# controller-adapter.net
KiCad netlist of a schematic drawn in EAGLE
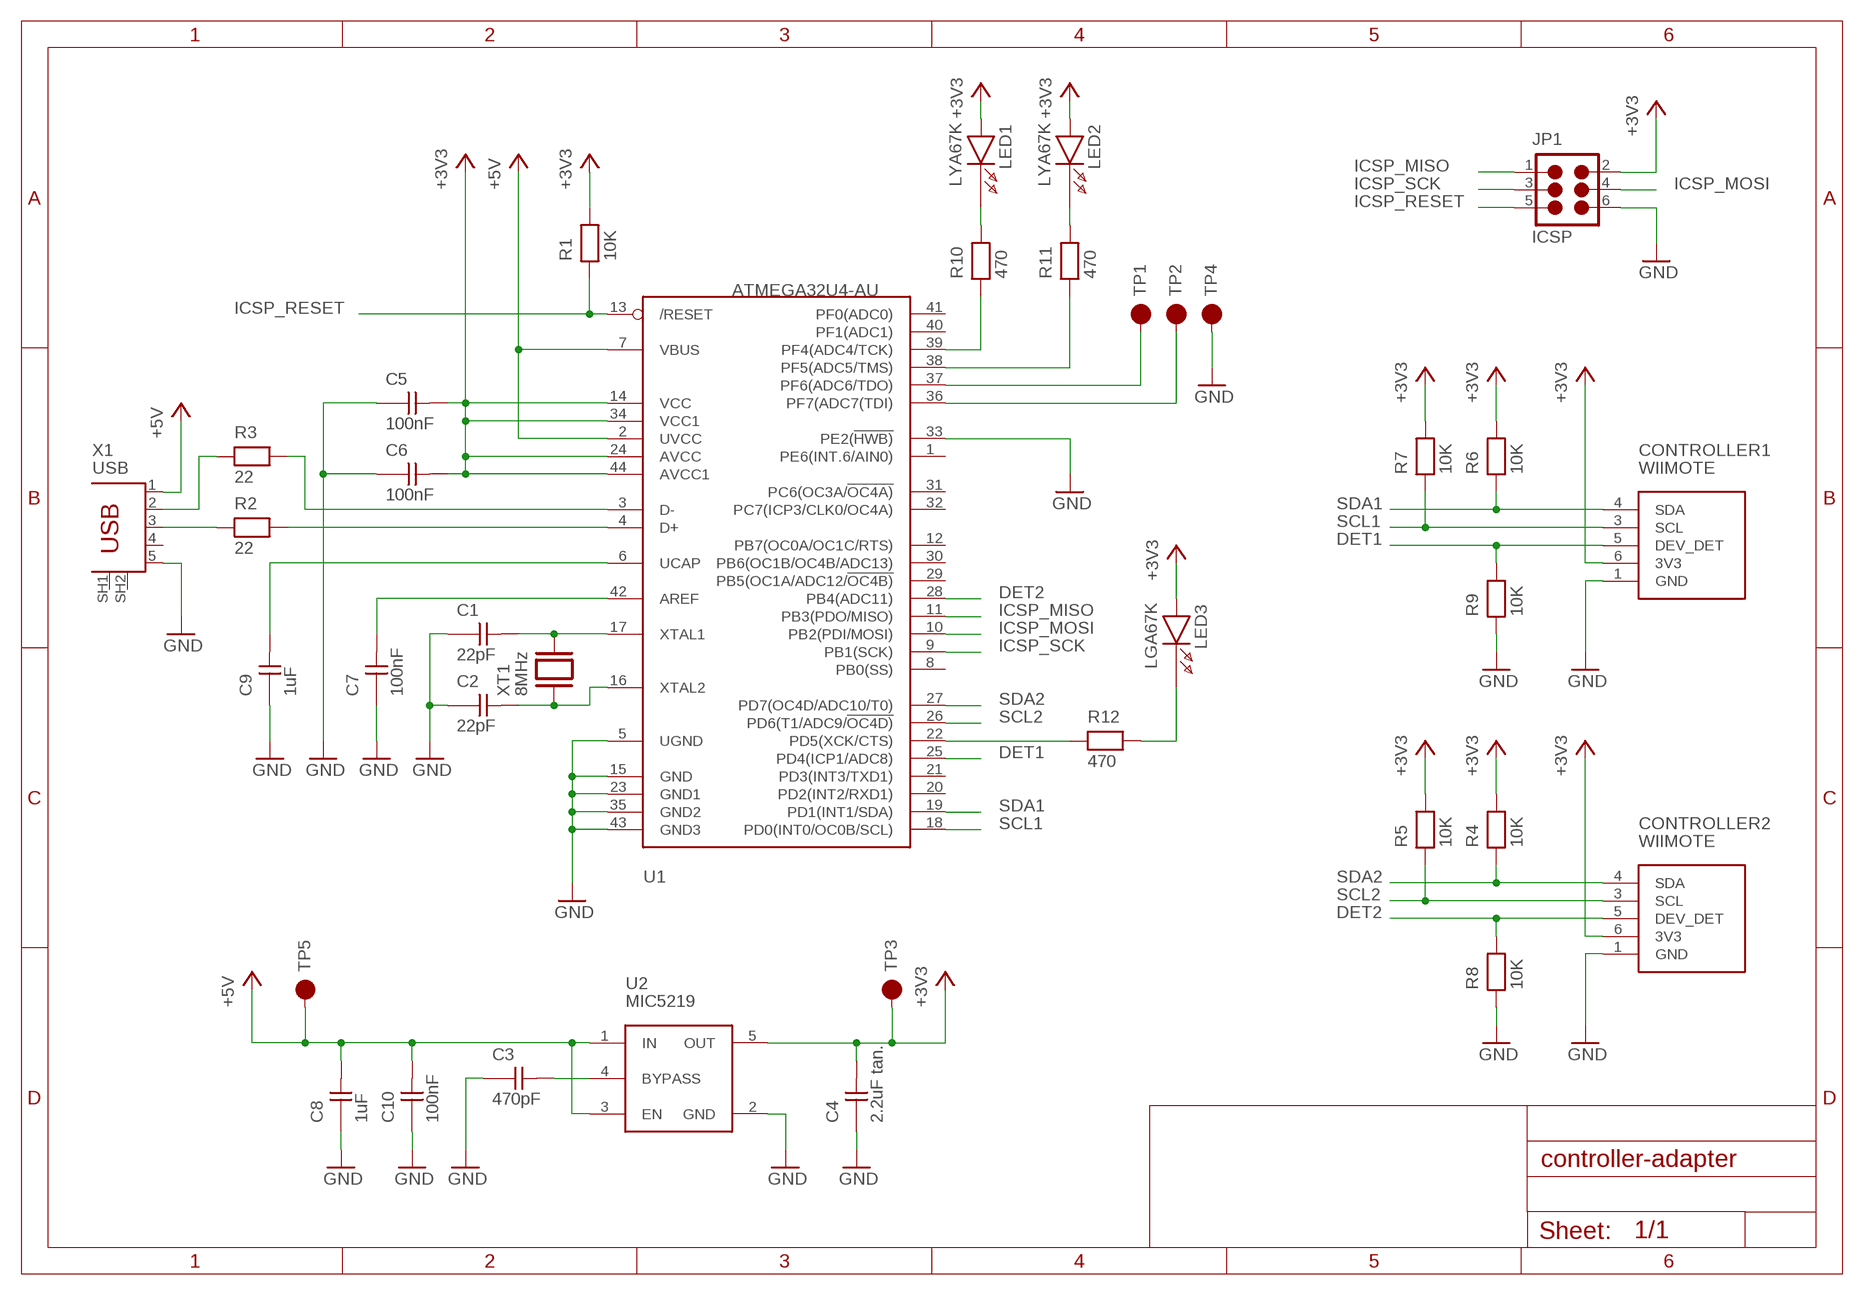
[diagram p0: schematic, sheet 1]

(export (version "E")
  (design (tool "Eeschema 10.0.6"))
  (components
    (comp (ref "C1")
      (value "22pF")
      (footprint "eagle-import:0603")
      (libsource (lib "eagle-import") (part "C0603"))
    )
    (comp (ref "C2")
      (value "22pF")
      (footprint "eagle-import:0603")
      (libsource (lib "eagle-import") (part "C0603"))
    )
    (comp (ref "C3")
      (value "470pF")
      (footprint "eagle-import:0603")
      (libsource (lib "eagle-import") (part "C0603"))
    )
    (comp (ref "C4")
      (value "2.2uF tan.")
      (footprint "eagle-import:1206")
      (libsource (lib "eagle-import") (part "C1206"))
    )
    (comp (ref "C5")
      (value "100nF")
      (footprint "eagle-import:0603")
      (libsource (lib "eagle-import") (part "C0603"))
    )
    (comp (ref "C6")
      (value "100nF")
      (footprint "eagle-import:0603")
      (libsource (lib "eagle-import") (part "C0603"))
    )
    (comp (ref "C7")
      (value "100nF")
      (footprint "eagle-import:0603")
      (libsource (lib "eagle-import") (part "C0603"))
    )
    (comp (ref "C8")
      (value "1uF")
      (footprint "eagle-import:0603")
      (libsource (lib "eagle-import") (part "C0603"))
    )
    (comp (ref "C9")
      (value "1uF")
      (footprint "eagle-import:0603")
      (libsource (lib "eagle-import") (part "C0603"))
    )
    (comp (ref "C10")
      (value "100nF")
      (footprint "eagle-import:0603")
      (libsource (lib "eagle-import") (part "C0603"))
    )
    (comp (ref "CONTROLLER1")
      (value "WIIMOTE")
      (footprint "eagle-import:WIIMOTE")
      (libsource (lib "eagle-import") (part "WIIMOTE"))
    )
    (comp (ref "CONTROLLER2")
      (value "WIIMOTE")
      (footprint "eagle-import:WIIMOTE")
      (libsource (lib "eagle-import") (part "WIIMOTE"))
    )
    (comp (ref "JP1")
      (value "ICSP")
      (footprint "eagle-import:JP6")
      (libsource (lib "eagle-import") (part "JP6"))
    )
    (comp (ref "LED1")
      (value "LYA67K")
      (footprint "eagle-import:SIDELED")
      (libsource (lib "eagle-import") (part "LEDSIDE"))
    )
    (comp (ref "LED2")
      (value "LYA67K")
      (footprint "eagle-import:SIDELED")
      (libsource (lib "eagle-import") (part "LEDSIDE"))
    )
    (comp (ref "LED3")
      (value "LGA67K")
      (footprint "eagle-import:SIDELED")
      (libsource (lib "eagle-import") (part "LEDSIDE"))
    )
    (comp (ref "R1")
      (value "10K")
      (footprint "eagle-import:0603")
      (libsource (lib "eagle-import") (part "R0603"))
    )
    (comp (ref "R2")
      (value "22")
      (footprint "eagle-import:0603")
      (libsource (lib "eagle-import") (part "R0603"))
    )
    (comp (ref "R3")
      (value "22")
      (footprint "eagle-import:0603")
      (libsource (lib "eagle-import") (part "R0603"))
    )
    (comp (ref "R4")
      (value "10K")
      (footprint "eagle-import:0603")
      (libsource (lib "eagle-import") (part "R0603"))
    )
    (comp (ref "R5")
      (value "10K")
      (footprint "eagle-import:0603")
      (libsource (lib "eagle-import") (part "R0603"))
    )
    (comp (ref "R6")
      (value "10K")
      (footprint "eagle-import:0603")
      (libsource (lib "eagle-import") (part "R0603"))
    )
    (comp (ref "R7")
      (value "10K")
      (footprint "eagle-import:0603")
      (libsource (lib "eagle-import") (part "R0603"))
    )
    (comp (ref "R8")
      (value "10K")
      (footprint "eagle-import:0603")
      (libsource (lib "eagle-import") (part "R0603"))
    )
    (comp (ref "R9")
      (value "10K")
      (footprint "eagle-import:0603")
      (libsource (lib "eagle-import") (part "R0603"))
    )
    (comp (ref "R10")
      (value "470")
      (footprint "eagle-import:0603")
      (libsource (lib "eagle-import") (part "R0603"))
    )
    (comp (ref "R11")
      (value "470")
      (footprint "eagle-import:0603")
      (libsource (lib "eagle-import") (part "R0603"))
    )
    (comp (ref "R12")
      (value "470")
      (footprint "eagle-import:0603")
      (libsource (lib "eagle-import") (part "R0603"))
    )
    (comp (ref "TP1")
      (value "A1")
      (footprint "eagle-import:TP1MM6")
      (libsource (lib "eagle-import") (part "TP1,6MM"))
    )
    (comp (ref "TP2")
      (value "A0")
      (footprint "eagle-import:TP1MM6")
      (libsource (lib "eagle-import") (part "TP1,6MM"))
    )
    (comp (ref "TP3")
      (value "+3V3")
      (footprint "eagle-import:TP1MM6")
      (libsource (lib "eagle-import") (part "TP1,6MM"))
    )
    (comp (ref "TP4")
      (value "GND")
      (footprint "eagle-import:TP1MM6")
      (libsource (lib "eagle-import") (part "TP1,6MM"))
    )
    (comp (ref "TP5")
      (value "+5V")
      (footprint "eagle-import:TP1MM6")
      (libsource (lib "eagle-import") (part "TP1,6MM"))
    )
    (comp (ref "U1")
      (value "ATMEGA32U4-AU")
      (footprint "eagle-import:TQFP44")
      (libsource (lib "eagle-import") (part "ATMEGA32U4-AU"))
    )
    (comp (ref "U2")
      (value "MIC5219")
      (footprint "eagle-import:SOT23-5")
      (libsource (lib "eagle-import") (part "MIC5219"))
    )
    (comp (ref "X1")
      (value "USB")
      (footprint "eagle-import:USB_MICRO_B_PIN")
      (libsource (lib "eagle-import") (part "USB_MICRO_B_MOLEX"))
    )
    (comp (ref "XT1")
      (value "8MHz")
      (footprint "eagle-import:ABM3B")
      (libsource (lib "eagle-import") (part "XTABM3B"))
    )
  )
  (nets
    (net (code "1") (name "+3V3") (class "Default")
      (node (ref "C4") (pin "2") (pinfunction "2_2") (pintype "passive"))
      (node (ref "C5") (pin "2") (pinfunction "2_2") (pintype "passive"))
      (node (ref "C6") (pin "2") (pinfunction "2_2") (pintype "passive"))
      (node (ref "CONTROLLER1") (pin "6") (pinfunction "3V3_6") (pintype "power_in"))
      (node (ref "CONTROLLER2") (pin "6") (pinfunction "3V3_6") (pintype "power_in"))
      (node (ref "JP1") (pin "2") (pinfunction "2_2") (pintype "bidirectional"))
      (node (ref "LED1") (pin "A") (pinfunction "A_A") (pintype "passive"))
      (node (ref "LED2") (pin "A") (pinfunction "A_A") (pintype "passive"))
      (node (ref "LED3") (pin "A") (pinfunction "A_A") (pintype "passive"))
      (node (ref "R1") (pin "2") (pinfunction "2_2") (pintype "passive"))
      (node (ref "R4") (pin "2") (pinfunction "2_2") (pintype "passive"))
      (node (ref "R5") (pin "2") (pinfunction "2_2") (pintype "passive"))
      (node (ref "R6") (pin "2") (pinfunction "2_2") (pintype "passive"))
      (node (ref "R7") (pin "2") (pinfunction "2_2") (pintype "passive"))
      (node (ref "TP3") (pin "1") (pinfunction "1_1") (pintype "bidirectional"))
      (node (ref "U1") (pin "14") (pinfunction "VCC_14") (pintype "bidirectional"))
      (node (ref "U1") (pin "24") (pinfunction "AVCC_24") (pintype "bidirectional"))
      (node (ref "U1") (pin "34") (pinfunction "VCC1_34") (pintype "bidirectional"))
      (node (ref "U1") (pin "44") (pinfunction "AVCC1_44") (pintype "bidirectional"))
      (node (ref "U2") (pin "5") (pinfunction "OUT_5") (pintype "tri_state"))
    )
    (net (code "2") (name "+5V") (class "Default")
      (node (ref "C10") (pin "2") (pinfunction "2_2") (pintype "passive"))
      (node (ref "C8") (pin "2") (pinfunction "2_2") (pintype "passive"))
      (node (ref "TP5") (pin "1") (pinfunction "1_1") (pintype "bidirectional"))
      (node (ref "U1") (pin "2") (pinfunction "UVCC_2") (pintype "bidirectional"))
      (node (ref "U1") (pin "7") (pinfunction "VBUS_7") (pintype "bidirectional"))
      (node (ref "U2") (pin "1") (pinfunction "IN_1") (pintype "power_in"))
      (node (ref "U2") (pin "3") (pinfunction "EN_3") (pintype "bidirectional"))
      (node (ref "X1") (pin "1") (pinfunction "VBUS_1") (pintype "bidirectional"))
    )
    (net (code "3") (name "/DET1") (class "Default")
      (node (ref "CONTROLLER1") (pin "5") (pinfunction "DEV_DET_5") (pintype "bidirectional"))
      (node (ref "R9") (pin "2") (pinfunction "2_2") (pintype "passive"))
      (node (ref "U1") (pin "25") (pinfunction "PD4(ICP1/ADC8)_25") (pintype "bidirectional"))
    )
    (net (code "4") (name "/DET2") (class "Default")
      (node (ref "CONTROLLER2") (pin "5") (pinfunction "DEV_DET_5") (pintype "bidirectional"))
      (node (ref "R8") (pin "2") (pinfunction "2_2") (pintype "passive"))
      (node (ref "U1") (pin "28") (pinfunction "PB4(ADC11)_28") (pintype "bidirectional"))
    )
    (net (code "5") (name "/ICSP_MISO") (class "Default")
      (node (ref "JP1") (pin "1") (pinfunction "1_1") (pintype "bidirectional"))
      (node (ref "U1") (pin "11") (pinfunction "PB3(PDO/MISO)_11") (pintype "bidirectional"))
    )
    (net (code "6") (name "/ICSP_MOSI") (class "Default")
      (node (ref "JP1") (pin "4") (pinfunction "4_4") (pintype "bidirectional"))
      (node (ref "U1") (pin "10") (pinfunction "PB2(PDI/MOSI)_10") (pintype "bidirectional"))
    )
    (net (code "7") (name "/ICSP_RESET") (class "Default")
      (node (ref "JP1") (pin "5") (pinfunction "5_5") (pintype "bidirectional"))
      (node (ref "R1") (pin "1") (pinfunction "1_1") (pintype "passive"))
      (node (ref "U1") (pin "13") (pinfunction "/RESET_13") (pintype "bidirectional"))
    )
    (net (code "8") (name "/ICSP_SCK") (class "Default")
      (node (ref "JP1") (pin "3") (pinfunction "3_3") (pintype "bidirectional"))
      (node (ref "U1") (pin "9") (pinfunction "PB1(SCK)_9") (pintype "bidirectional"))
    )
    (net (code "9") (name "/SCL1") (class "Default")
      (node (ref "CONTROLLER1") (pin "3") (pinfunction "SCL_3") (pintype "bidirectional"))
      (node (ref "R7") (pin "1") (pinfunction "1_1") (pintype "passive"))
      (node (ref "U1") (pin "18") (pinfunction "PD0(INT0/OC0B/SCL)_18") (pintype "bidirectional"))
    )
    (net (code "10") (name "/SCL2") (class "Default")
      (node (ref "CONTROLLER2") (pin "3") (pinfunction "SCL_3") (pintype "bidirectional"))
      (node (ref "R5") (pin "1") (pinfunction "1_1") (pintype "passive"))
      (node (ref "U1") (pin "26") (pinfunction "PD6(T1/ADC9/~{OC4D})_26") (pintype "bidirectional"))
    )
    (net (code "11") (name "/SDA1") (class "Default")
      (node (ref "CONTROLLER1") (pin "4") (pinfunction "SDA_4") (pintype "bidirectional"))
      (node (ref "R6") (pin "1") (pinfunction "1_1") (pintype "passive"))
      (node (ref "U1") (pin "19") (pinfunction "PD1(INT1/SDA)_19") (pintype "bidirectional"))
    )
    (net (code "12") (name "/SDA2") (class "Default")
      (node (ref "CONTROLLER2") (pin "4") (pinfunction "SDA_4") (pintype "bidirectional"))
      (node (ref "R4") (pin "1") (pinfunction "1_1") (pintype "passive"))
      (node (ref "U1") (pin "27") (pinfunction "PD7(OC4D/ADC10/T0)_27") (pintype "bidirectional"))
    )
    (net (code "13") (name "GND") (class "Default")
      (node (ref "C1") (pin "1") (pinfunction "1_1") (pintype "passive"))
      (node (ref "C10") (pin "1") (pinfunction "1_1") (pintype "passive"))
      (node (ref "C2") (pin "1") (pinfunction "1_1") (pintype "passive"))
      (node (ref "C3") (pin "1") (pinfunction "1_1") (pintype "passive"))
      (node (ref "C4") (pin "1") (pinfunction "1_1") (pintype "passive"))
      (node (ref "C5") (pin "1") (pinfunction "1_1") (pintype "passive"))
      (node (ref "C6") (pin "1") (pinfunction "1_1") (pintype "passive"))
      (node (ref "C7") (pin "1") (pinfunction "1_1") (pintype "passive"))
      (node (ref "C8") (pin "1") (pinfunction "1_1") (pintype "passive"))
      (node (ref "C9") (pin "1") (pinfunction "1_1") (pintype "passive"))
      (node (ref "CONTROLLER1") (pin "1") (pinfunction "GND_1") (pintype "power_in"))
      (node (ref "CONTROLLER2") (pin "1") (pinfunction "GND_1") (pintype "power_in"))
      (node (ref "JP1") (pin "6") (pinfunction "6_6") (pintype "bidirectional"))
      (node (ref "R8") (pin "1") (pinfunction "1_1") (pintype "passive"))
      (node (ref "R9") (pin "1") (pinfunction "1_1") (pintype "passive"))
      (node (ref "TP4") (pin "1") (pinfunction "1_1") (pintype "bidirectional"))
      (node (ref "U1") (pin "15") (pinfunction "GND_15") (pintype "bidirectional"))
      (node (ref "U1") (pin "23") (pinfunction "GND1_23") (pintype "bidirectional"))
      (node (ref "U1") (pin "33") (pinfunction "PE2(~{HWB})_33") (pintype "bidirectional"))
      (node (ref "U1") (pin "35") (pinfunction "GND2_35") (pintype "bidirectional"))
      (node (ref "U1") (pin "43") (pinfunction "GND3_43") (pintype "bidirectional"))
      (node (ref "U1") (pin "5") (pinfunction "UGND_5") (pintype "bidirectional"))
      (node (ref "U2") (pin "2") (pinfunction "GND_2") (pintype "power_in"))
      (node (ref "X1") (pin "5") (pinfunction "GND_5") (pintype "bidirectional"))
    )
    (net (code "14") (name "Net-(LED1-PadK)") (class "Default")
      (node (ref "LED1") (pin "K") (pinfunction "K_K") (pintype "passive"))
      (node (ref "R10") (pin "2") (pinfunction "2_2") (pintype "passive"))
    )
    (net (code "15") (name "Net-(LED2-PadK)") (class "Default")
      (node (ref "LED2") (pin "K") (pinfunction "K_K") (pintype "passive"))
      (node (ref "R11") (pin "2") (pinfunction "2_2") (pintype "passive"))
    )
    (net (code "16") (name "Net-(LED3-PadK)") (class "Default")
      (node (ref "LED3") (pin "K") (pinfunction "K_K") (pintype "passive"))
      (node (ref "R12") (pin "2") (pinfunction "2_2") (pintype "passive"))
    )
    (net (code "17") (name "Net-(U1-AREF)") (class "Default")
      (node (ref "C7") (pin "2") (pinfunction "2_2") (pintype "passive"))
      (node (ref "U1") (pin "42") (pinfunction "AREF_42") (pintype "bidirectional"))
    )
    (net (code "18") (name "Net-(U1-D+)") (class "Default")
      (node (ref "R2") (pin "2") (pinfunction "2_2") (pintype "passive"))
      (node (ref "U1") (pin "4") (pinfunction "D+_4") (pintype "bidirectional"))
    )
    (net (code "19") (name "Net-(U1-D-)") (class "Default")
      (node (ref "R3") (pin "2") (pinfunction "2_2") (pintype "passive"))
      (node (ref "U1") (pin "3") (pinfunction "D-_3") (pintype "bidirectional"))
    )
    (net (code "20") (name "Net-(U1-PD5(XCK{slash}CTS))") (class "Default")
      (node (ref "R12") (pin "1") (pinfunction "1_1") (pintype "passive"))
      (node (ref "U1") (pin "22") (pinfunction "PD5(XCK/CTS)_22") (pintype "bidirectional"))
    )
    (net (code "21") (name "Net-(U1-PF4(ADC4{slash}TCK))") (class "Default")
      (node (ref "R10") (pin "1") (pinfunction "1_1") (pintype "passive"))
      (node (ref "U1") (pin "39") (pinfunction "PF4(ADC4/TCK)_39") (pintype "bidirectional"))
    )
    (net (code "22") (name "Net-(U1-PF5(ADC5{slash}TMS))") (class "Default")
      (node (ref "R11") (pin "1") (pinfunction "1_1") (pintype "passive"))
      (node (ref "U1") (pin "38") (pinfunction "PF5(ADC5/TMS)_38") (pintype "bidirectional"))
    )
    (net (code "23") (name "Net-(U1-PF6(ADC6{slash}TDO))") (class "Default")
      (node (ref "TP1") (pin "1") (pinfunction "1_1") (pintype "bidirectional"))
      (node (ref "U1") (pin "37") (pinfunction "PF6(ADC6/TDO)_37") (pintype "bidirectional"))
    )
    (net (code "24") (name "Net-(U1-PF7(ADC7(TDI))") (class "Default")
      (node (ref "TP2") (pin "1") (pinfunction "1_1") (pintype "bidirectional"))
      (node (ref "U1") (pin "36") (pinfunction "PF7(ADC7(TDI)_36") (pintype "bidirectional"))
    )
    (net (code "25") (name "Net-(U1-UCAP)") (class "Default")
      (node (ref "C9") (pin "2") (pinfunction "2_2") (pintype "passive"))
      (node (ref "U1") (pin "6") (pinfunction "UCAP_6") (pintype "bidirectional"))
    )
    (net (code "26") (name "Net-(U1-XTAL1)") (class "Default")
      (node (ref "C1") (pin "2") (pinfunction "2_2") (pintype "passive"))
      (node (ref "U1") (pin "17") (pinfunction "XTAL1_17") (pintype "bidirectional"))
      (node (ref "XT1") (pin "3") (pinfunction "2_3") (pintype "passive"))
    )
    (net (code "27") (name "Net-(U1-XTAL2)") (class "Default")
      (node (ref "C2") (pin "2") (pinfunction "2_2") (pintype "passive"))
      (node (ref "U1") (pin "16") (pinfunction "XTAL2_16") (pintype "bidirectional"))
      (node (ref "XT1") (pin "1") (pinfunction "1_1") (pintype "passive"))
    )
    (net (code "28") (name "Net-(U2-BYPASS)") (class "Default")
      (node (ref "C3") (pin "2") (pinfunction "2_2") (pintype "passive"))
      (node (ref "U2") (pin "4") (pinfunction "BYPASS_4") (pintype "bidirectional"))
    )
    (net (code "29") (name "Net-(X1-D+)") (class "Default")
      (node (ref "R2") (pin "1") (pinfunction "1_1") (pintype "passive"))
      (node (ref "X1") (pin "3") (pinfunction "D+_3") (pintype "bidirectional"))
    )
    (net (code "30") (name "Net-(X1-D-)") (class "Default")
      (node (ref "R3") (pin "1") (pinfunction "1_1") (pintype "passive"))
      (node (ref "X1") (pin "2") (pinfunction "D-_2") (pintype "bidirectional"))
    )
    (net (code "31") (name "unconnected-(U1-PB0(SS)-Pad8)") (class "Default")
      (node (ref "U1") (pin "8") (pinfunction "PB0(SS)_8") (pintype "bidirectional"))
    )
    (net (code "32") (name "unconnected-(U1-PB5(OC1A{slash}ADC12{slash}~{OC4B})-Pad29)") (class "Default")
      (node (ref "U1") (pin "29") (pinfunction "PB5(OC1A/ADC12/~{OC4B})_29") (pintype "bidirectional"))
    )
    (net (code "33") (name "unconnected-(U1-PB6(OC1B{slash}OC4B{slash}ADC13)-Pad30)") (class "Default")
      (node (ref "U1") (pin "30") (pinfunction "PB6(OC1B/OC4B/ADC13)_30") (pintype "bidirectional"))
    )
    (net (code "34") (name "unconnected-(U1-PB7(OC0A{slash}OC1C{slash}RTS)-Pad12)") (class "Default")
      (node (ref "U1") (pin "12") (pinfunction "PB7(OC0A/OC1C/RTS)_12") (pintype "bidirectional"))
    )
    (net (code "35") (name "unconnected-(U1-PC6(OC3A{slash}~{OC4A})-Pad31)") (class "Default")
      (node (ref "U1") (pin "31") (pinfunction "PC6(OC3A/~{OC4A})_31") (pintype "bidirectional"))
    )
    (net (code "36") (name "unconnected-(U1-PC7(ICP3{slash}CLK0{slash}OC4A)-Pad32)") (class "Default")
      (node (ref "U1") (pin "32") (pinfunction "PC7(ICP3/CLK0/OC4A)_32") (pintype "bidirectional"))
    )
    (net (code "37") (name "unconnected-(U1-PD2(INT2{slash}RXD1)-Pad20)") (class "Default")
      (node (ref "U1") (pin "20") (pinfunction "PD2(INT2/RXD1)_20") (pintype "bidirectional"))
    )
    (net (code "38") (name "unconnected-(U1-PD3(INT3{slash}TXD1)-Pad21)") (class "Default")
      (node (ref "U1") (pin "21") (pinfunction "PD3(INT3/TXD1)_21") (pintype "bidirectional"))
    )
    (net (code "39") (name "unconnected-(U1-PE6(INT.6{slash}AIN0)-Pad1)") (class "Default")
      (node (ref "U1") (pin "1") (pinfunction "PE6(INT.6/AIN0)_1") (pintype "bidirectional"))
    )
    (net (code "40") (name "unconnected-(U1-PF0(ADC0)-Pad41)") (class "Default")
      (node (ref "U1") (pin "41") (pinfunction "PF0(ADC0)_41") (pintype "bidirectional"))
    )
    (net (code "41") (name "unconnected-(U1-PF1(ADC1)-Pad40)") (class "Default")
      (node (ref "U1") (pin "40") (pinfunction "PF1(ADC1)_40") (pintype "bidirectional"))
    )
    (net (code "42") (name "unconnected-(X1-ID-Pad4)") (class "Default")
      (node (ref "X1") (pin "4") (pinfunction "ID_4") (pintype "bidirectional"))
    )
    (net (code "43") (name "unconnected-(X1-TAB-PadSH1)") (class "Default")
      (node (ref "X1") (pin "SH1") (pinfunction "TAB_SH1") (pintype "bidirectional"))
    )
    (net (code "44") (name "unconnected-(X1-TAB-PadSH2)") (class "Default")
      (node (ref "X1") (pin "SH2") (pinfunction "TAB_SH2") (pintype "bidirectional"))
    )
  )
)
